# SSR_OUTPUTS.net
KiCad netlist of a schematic drawn in Altium Designer
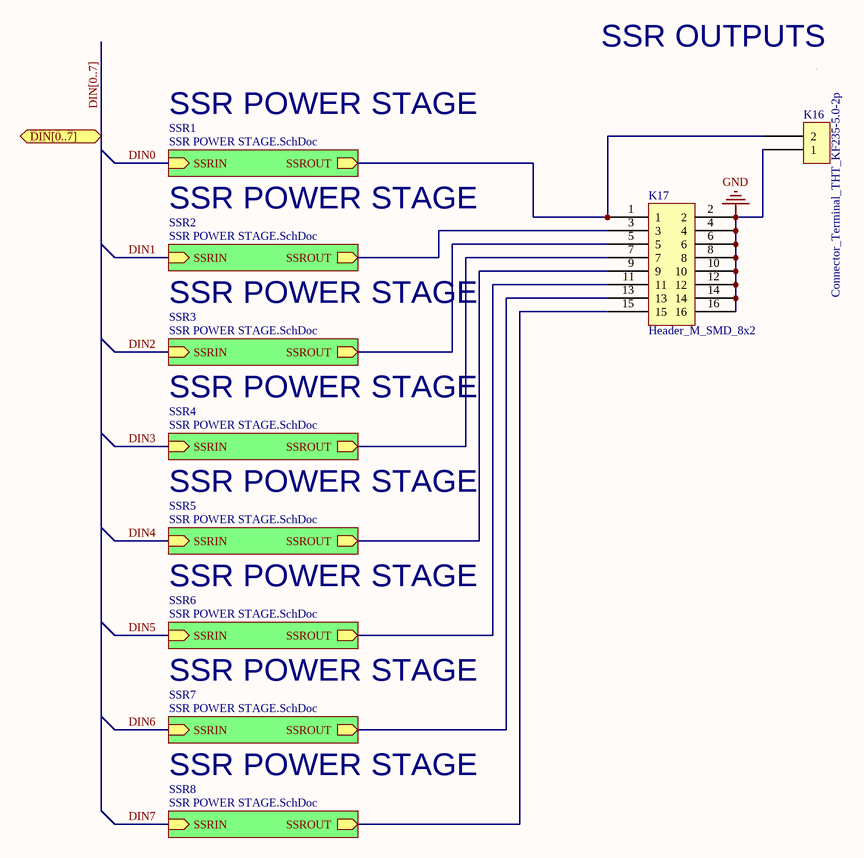
[diagram p0: SSR OUTPUTS.SchDoc]

(export (version "E")
  (design (tool "Eeschema 10.0.6"))
  (components
    (comp (ref "K16")
      (value "Connector_Terminal_THT_KF235-5.0-2p")
      (footprint "KF235-5.0-2p")
      (libsource (lib "RVA_Altium_Library") (part "Connector_Terminal_THT_KF235-5.0-2p"))
    )
    (comp (ref "K17")
      (value "Header_M_SMD_8x2")
      (footprint "Header_Male_2.54 8x2")
      (description "SMD Header 8x2")
      (libsource (lib "RVA_Altium_Library") (part "Header_M_SMD_8x2"))
    )
  )
  (nets
    (net (code "10") (name "/SSROUT") (class "Default")
      (node (ref "K17") (pin "15") (pinfunction "15_15") (pintype "passive"))
    )
    (net (code "11") (name "/SSROUT_1") (class "Default")
      (node (ref "K17") (pin "7") (pinfunction "7_7") (pintype "passive"))
    )
    (net (code "12") (name "/SSROUT_2") (class "Default")
      (node (ref "K17") (pin "9") (pinfunction "9_9") (pintype "passive"))
    )
    (net (code "13") (name "/SSROUT_3") (class "Default")
      (node (ref "K17") (pin "11") (pinfunction "11_11") (pintype "passive"))
    )
    (net (code "14") (name "/SSROUT_4") (class "Default")
      (node (ref "K17") (pin "3") (pinfunction "3_3") (pintype "passive"))
    )
    (net (code "15") (name "/SSROUT_5") (class "Default")
      (node (ref "K17") (pin "5") (pinfunction "5_5") (pintype "passive"))
    )
    (net (code "16") (name "/SSROUT_6") (class "Default")
      (node (ref "K17") (pin "13") (pinfunction "13_13") (pintype "passive"))
    )
    (net (code "17") (name "/SSROUT_7") (class "Default")
      (node (ref "K16") (pin "2") (pinfunction "2_2") (pintype "passive"))
      (node (ref "K17") (pin "1") (pinfunction "1_1") (pintype "passive"))
    )
    (net (code "18") (name "GND") (class "Default")
      (node (ref "K16") (pin "1") (pinfunction "1_1") (pintype "passive"))
      (node (ref "K17") (pin "10") (pinfunction "10_10") (pintype "passive"))
      (node (ref "K17") (pin "12") (pinfunction "12_12") (pintype "passive"))
      (node (ref "K17") (pin "14") (pinfunction "14_14") (pintype "passive"))
      (node (ref "K17") (pin "16") (pinfunction "16_16") (pintype "passive"))
      (node (ref "K17") (pin "2") (pinfunction "2_2") (pintype "passive"))
      (node (ref "K17") (pin "4") (pinfunction "4_4") (pintype "passive"))
      (node (ref "K17") (pin "6") (pinfunction "6_6") (pintype "passive"))
      (node (ref "K17") (pin "8") (pinfunction "8_8") (pintype "passive"))
    )
  )
)
